# M706K.net
KiCad netlist of a schematic drawn in EAGLE
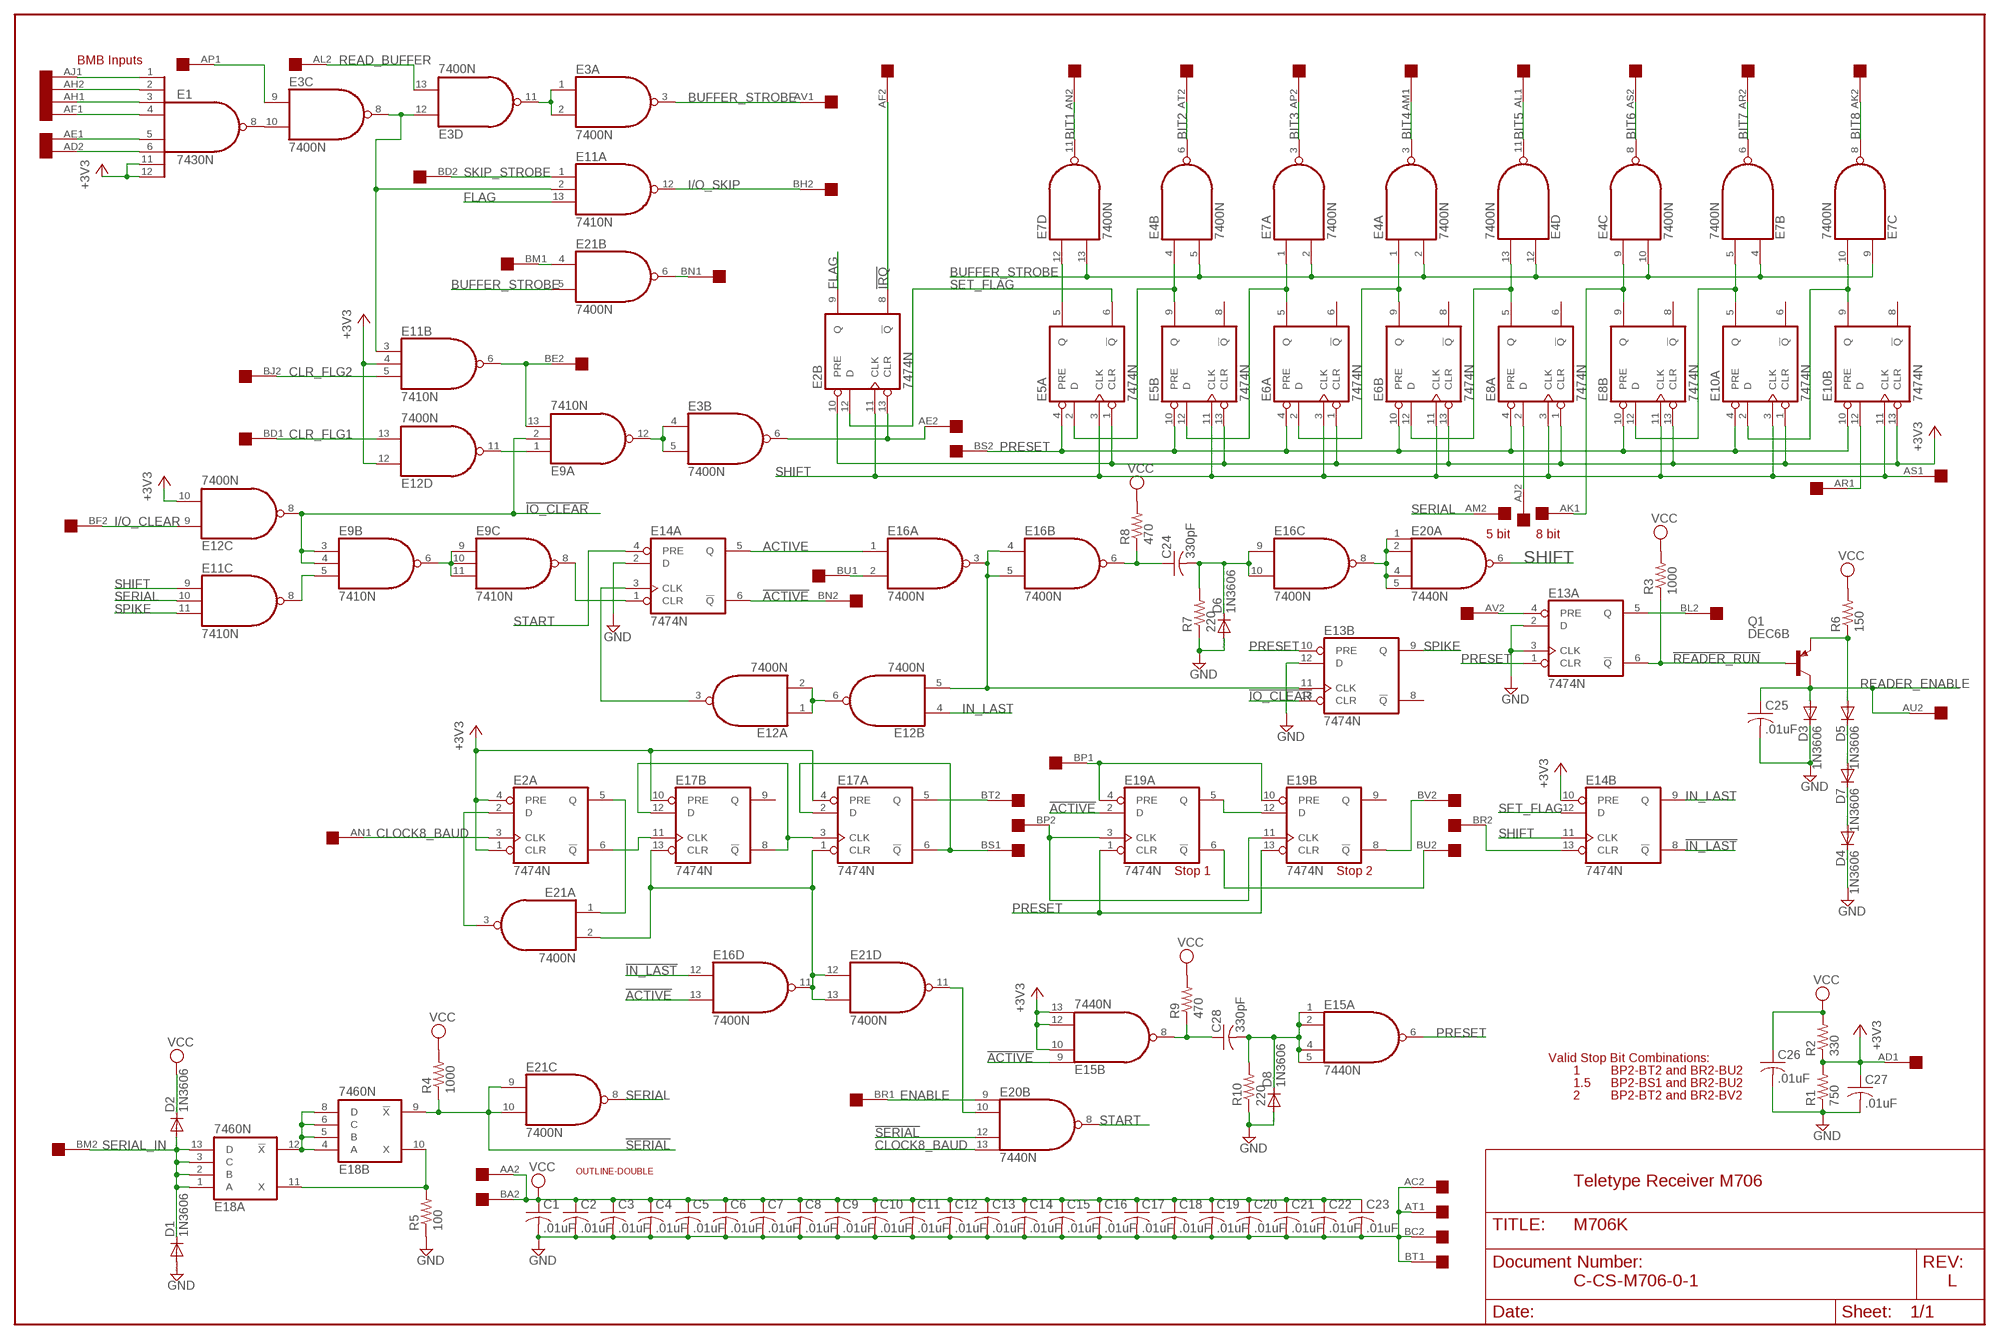
[diagram p0: schematic, sheet 1]

(export (version "E")
  (design (tool "Eeschema 10.0.6"))
  (components
    (comp (ref "C1")
      (value ".01uF")
      (footprint "eagle-import:C050-025X075")
      (libsource (lib "eagle-import") (part "C-US050-025X075"))
    )
    (comp (ref "C2")
      (value ".01uF")
      (footprint "eagle-import:C050-025X075")
      (libsource (lib "eagle-import") (part "C-US050-025X075"))
    )
    (comp (ref "C3")
      (value ".01uF")
      (footprint "eagle-import:C050-025X075")
      (libsource (lib "eagle-import") (part "C-US050-025X075"))
    )
    (comp (ref "C4")
      (value ".01uF")
      (footprint "eagle-import:C050-025X075")
      (libsource (lib "eagle-import") (part "C-US050-025X075"))
    )
    (comp (ref "C5")
      (value ".01uF")
      (footprint "eagle-import:C050-025X075")
      (libsource (lib "eagle-import") (part "C-US050-025X075"))
    )
    (comp (ref "C6")
      (value ".01uF")
      (footprint "eagle-import:C050-025X075")
      (libsource (lib "eagle-import") (part "C-US050-025X075"))
    )
    (comp (ref "C7")
      (value ".01uF")
      (footprint "eagle-import:C050-025X075")
      (libsource (lib "eagle-import") (part "C-US050-025X075"))
    )
    (comp (ref "C8")
      (value ".01uF")
      (footprint "eagle-import:C050-025X075")
      (libsource (lib "eagle-import") (part "C-US050-025X075"))
    )
    (comp (ref "C9")
      (value ".01uF")
      (footprint "eagle-import:C050-025X075")
      (libsource (lib "eagle-import") (part "C-US050-025X075"))
    )
    (comp (ref "C10")
      (value ".01uF")
      (footprint "eagle-import:C050-025X075")
      (libsource (lib "eagle-import") (part "C-US050-025X075"))
    )
    (comp (ref "C11")
      (value ".01uF")
      (footprint "eagle-import:C050-025X075")
      (libsource (lib "eagle-import") (part "C-US050-025X075"))
    )
    (comp (ref "C12")
      (value ".01uF")
      (footprint "eagle-import:C050-025X075")
      (libsource (lib "eagle-import") (part "C-US050-025X075"))
    )
    (comp (ref "C13")
      (value ".01uF")
      (footprint "eagle-import:C050-025X075")
      (libsource (lib "eagle-import") (part "C-US050-025X075"))
    )
    (comp (ref "C14")
      (value ".01uF")
      (footprint "eagle-import:C050-025X075")
      (libsource (lib "eagle-import") (part "C-US050-025X075"))
    )
    (comp (ref "C15")
      (value ".01uF")
      (footprint "eagle-import:C050-025X075")
      (libsource (lib "eagle-import") (part "C-US050-025X075"))
    )
    (comp (ref "C16")
      (value ".01uF")
      (footprint "eagle-import:C050-025X075")
      (libsource (lib "eagle-import") (part "C-US050-025X075"))
    )
    (comp (ref "C17")
      (value ".01uF")
      (footprint "eagle-import:C050-025X075")
      (libsource (lib "eagle-import") (part "C-US050-025X075"))
    )
    (comp (ref "C18")
      (value ".01uF")
      (footprint "eagle-import:C050-025X075")
      (libsource (lib "eagle-import") (part "C-US050-025X075"))
    )
    (comp (ref "C19")
      (value ".01uF")
      (footprint "eagle-import:C050-025X075")
      (libsource (lib "eagle-import") (part "C-US050-025X075"))
    )
    (comp (ref "C20")
      (value ".01uF")
      (footprint "eagle-import:C050-025X075")
      (libsource (lib "eagle-import") (part "C-US050-025X075"))
    )
    (comp (ref "C21")
      (value ".01uF")
      (footprint "eagle-import:C050-025X075")
      (libsource (lib "eagle-import") (part "C-US050-025X075"))
    )
    (comp (ref "C22")
      (value ".01uF")
      (footprint "eagle-import:C050-025X075")
      (libsource (lib "eagle-import") (part "C-US050-025X075"))
    )
    (comp (ref "C23")
      (value ".01uF")
      (footprint "eagle-import:C050-025X075")
      (libsource (lib "eagle-import") (part "C-US050-025X075"))
    )
    (comp (ref "C24")
      (value "330pF")
      (footprint "eagle-import:C050-025X075")
      (libsource (lib "eagle-import") (part "C-US050-025X075"))
    )
    (comp (ref "C25")
      (value ".01uF")
      (footprint "eagle-import:C050-025X075")
      (libsource (lib "eagle-import") (part "C-US050-025X075"))
    )
    (comp (ref "C26")
      (value ".01uF")
      (footprint "eagle-import:C050-025X075")
      (libsource (lib "eagle-import") (part "C-US050-025X075"))
    )
    (comp (ref "C27")
      (value ".01uF")
      (footprint "eagle-import:C050-025X075")
      (libsource (lib "eagle-import") (part "C-US050-025X075"))
    )
    (comp (ref "C28")
      (value "330pF")
      (footprint "eagle-import:C050-025X075")
      (libsource (lib "eagle-import") (part "C-US050-025X075"))
    )
    (comp (ref "D1")
      (value "1N3606")
      (footprint "eagle-import:DO35-10")
      (libsource (lib "eagle-import") (part "1N4148DO35-10"))
    )
    (comp (ref "D2")
      (value "1N3606")
      (footprint "eagle-import:DO35-10")
      (libsource (lib "eagle-import") (part "1N4148DO35-10"))
    )
    (comp (ref "D3")
      (value "1N3606")
      (footprint "eagle-import:DO35-10")
      (libsource (lib "eagle-import") (part "1N4148DO35-10"))
    )
    (comp (ref "D4")
      (value "1N3606")
      (footprint "eagle-import:DO35-10")
      (libsource (lib "eagle-import") (part "1N4148DO35-10"))
    )
    (comp (ref "D5")
      (value "1N3606")
      (footprint "eagle-import:DO35-10")
      (libsource (lib "eagle-import") (part "1N4148DO35-10"))
    )
    (comp (ref "D6")
      (value "1N3606")
      (footprint "eagle-import:DO35-10")
      (libsource (lib "eagle-import") (part "1N4148DO35-10"))
    )
    (comp (ref "D7")
      (value "1N3606")
      (footprint "eagle-import:DO35-10")
      (libsource (lib "eagle-import") (part "1N4148DO35-10"))
    )
    (comp (ref "D8")
      (value "1N3606")
      (footprint "eagle-import:DO35-10")
      (libsource (lib "eagle-import") (part "1N4148DO35-10"))
    )
    (comp (ref "E1")
      (value "7430N")
      (footprint "eagle-import:DIL14")
      (libsource (lib "eagle-import") (part "7430N"))
    )
    (comp (ref "E2")
      (value "7474N")
      (footprint "eagle-import:DIL14")
      (libsource (lib "eagle-import") (part "7474NS"))
    )
    (comp (ref "E3")
      (value "7400N")
      (footprint "eagle-import:DIL14")
      (libsource (lib "eagle-import") (part "7400N"))
    )
    (comp (ref "E4")
      (value "7400N")
      (footprint "eagle-import:DIL14")
      (libsource (lib "eagle-import") (part "7400N"))
    )
    (comp (ref "E5")
      (value "7474N")
      (footprint "eagle-import:DIL14")
      (libsource (lib "eagle-import") (part "7474NS"))
    )
    (comp (ref "E6")
      (value "7474N")
      (footprint "eagle-import:DIL14")
      (libsource (lib "eagle-import") (part "7474NS"))
    )
    (comp (ref "E7")
      (value "7400N")
      (footprint "eagle-import:DIL14")
      (libsource (lib "eagle-import") (part "7400N"))
    )
    (comp (ref "E8")
      (value "7474N")
      (footprint "eagle-import:DIL14")
      (libsource (lib "eagle-import") (part "7474NS"))
    )
    (comp (ref "E9")
      (value "7410N")
      (footprint "eagle-import:DIL14")
      (libsource (lib "eagle-import") (part "7410N"))
    )
    (comp (ref "E10")
      (value "7474N")
      (footprint "eagle-import:DIL14")
      (libsource (lib "eagle-import") (part "7474NS"))
    )
    (comp (ref "E11")
      (value "7410N")
      (footprint "eagle-import:DIL14")
      (libsource (lib "eagle-import") (part "7410N"))
    )
    (comp (ref "E12")
      (value "7400N")
      (footprint "eagle-import:DIL14")
      (libsource (lib "eagle-import") (part "7400N"))
    )
    (comp (ref "E13")
      (value "7474N")
      (footprint "eagle-import:DIL14")
      (libsource (lib "eagle-import") (part "7474NS"))
    )
    (comp (ref "E14")
      (value "7474N")
      (footprint "eagle-import:DIL14")
      (libsource (lib "eagle-import") (part "7474NS"))
    )
    (comp (ref "E15")
      (value "7440N")
      (footprint "eagle-import:DIL14")
      (libsource (lib "eagle-import") (part "7420NS"))
    )
    (comp (ref "E16")
      (value "7400N")
      (footprint "eagle-import:DIL14")
      (libsource (lib "eagle-import") (part "7400N"))
    )
    (comp (ref "E17")
      (value "7474N")
      (footprint "eagle-import:DIL14")
      (libsource (lib "eagle-import") (part "7474NS"))
    )
    (comp (ref "E18")
      (value "7460N")
      (footprint "eagle-import:DIL14")
      (libsource (lib "eagle-import") (part "7460N"))
    )
    (comp (ref "E19")
      (value "7474N")
      (footprint "eagle-import:DIL14")
      (libsource (lib "eagle-import") (part "7474NS"))
    )
    (comp (ref "E20")
      (value "7440N")
      (footprint "eagle-import:DIL14")
      (libsource (lib "eagle-import") (part "7420NS"))
    )
    (comp (ref "E21")
      (value "7400N")
      (footprint "eagle-import:DIL14")
      (libsource (lib "eagle-import") (part "7400N"))
    )
    (comp (ref "Q1")
      (value "DEC6B")
      (footprint "eagle-import:TO39")
      (libsource (lib "eagle-import") (part "2N2904"))
    )
    (comp (ref "R1")
      (value "750")
      (footprint "eagle-import:0207_10")
      (libsource (lib "eagle-import") (part "R-US_0207/10"))
    )
    (comp (ref "R2")
      (value "330")
      (footprint "eagle-import:0207_10")
      (libsource (lib "eagle-import") (part "R-US_0207/10"))
    )
    (comp (ref "R3")
      (value "1000")
      (footprint "eagle-import:0207_10")
      (libsource (lib "eagle-import") (part "R-US_0207/10"))
    )
    (comp (ref "R4")
      (value "1000")
      (footprint "eagle-import:0207_10")
      (libsource (lib "eagle-import") (part "R-US_0207/10"))
    )
    (comp (ref "R5")
      (value "100")
      (footprint "eagle-import:0207_10")
      (libsource (lib "eagle-import") (part "R-US_0207/10"))
    )
    (comp (ref "R6")
      (value "150")
      (footprint "eagle-import:0207_10")
      (libsource (lib "eagle-import") (part "R-US_0207/10"))
    )
    (comp (ref "R7")
      (value "220")
      (footprint "eagle-import:0207_10")
      (libsource (lib "eagle-import") (part "R-US_0207/10"))
    )
    (comp (ref "R8")
      (value "470")
      (footprint "eagle-import:0207_10")
      (libsource (lib "eagle-import") (part "R-US_0207/10"))
    )
    (comp (ref "R9")
      (value "470")
      (footprint "eagle-import:0207_10")
      (libsource (lib "eagle-import") (part "R-US_0207/10"))
    )
    (comp (ref "R10")
      (value "220")
      (footprint "eagle-import:0207_10")
      (libsource (lib "eagle-import") (part "R-US_0207/10"))
    )
    (comp (ref "U$1")
      (value "OUTLINE-DOUBLE")
      (footprint "eagle-import:DOUBLE")
      (libsource (lib "eagle-import") (part "OUTLINE-DOUBLE"))
    )
    (comp (ref "U$2")
      (value "DOUBLE")
      (footprint "eagle-import:EDGE-CON4")
      (libsource (lib "eagle-import") (part "DOUBLE"))
    )
  )
  (nets
    (net (code "1") (name "+3V3") (class "Default")
      (node (ref "C27") (pin "1") (pinfunction "1_1") (pintype "passive"))
      (node (ref "E1") (pin "11") (pinfunction "I6_11") (pintype "input"))
      (node (ref "E1") (pin "12") (pinfunction "I7_12") (pintype "input"))
      (node (ref "E10") (pin "1") (pinfunction "CLR_1") (pintype "input"))
      (node (ref "E10") (pin "13") (pinfunction "CLR_13") (pintype "input"))
      (node (ref "E11") (pin "4") (pinfunction "I1_4") (pintype "input"))
      (node (ref "E12") (pin "10") (pinfunction "I1_10") (pintype "input"))
      (node (ref "E12") (pin "12") (pinfunction "I0_12") (pintype "input"))
      (node (ref "E14") (pin "10") (pinfunction "PRE_10") (pintype "input"))
      (node (ref "E15") (pin "10") (pinfunction "I1_10") (pintype "input"))
      (node (ref "E15") (pin "12") (pinfunction "I2_12") (pintype "input"))
      (node (ref "E15") (pin "13") (pinfunction "I3_13") (pintype "input"))
      (node (ref "E17") (pin "10") (pinfunction "PRE_10") (pintype "input"))
      (node (ref "E17") (pin "4") (pinfunction "PRE_4") (pintype "input"))
      (node (ref "E2") (pin "1") (pinfunction "CLR_1") (pintype "input"))
      (node (ref "E2") (pin "10") (pinfunction "PRE_10") (pintype "input"))
      (node (ref "E2") (pin "4") (pinfunction "PRE_4") (pintype "input"))
      (node (ref "E5") (pin "1") (pinfunction "CLR_1") (pintype "input"))
      (node (ref "E5") (pin "13") (pinfunction "CLR_13") (pintype "input"))
      (node (ref "E6") (pin "1") (pinfunction "CLR_1") (pintype "input"))
      (node (ref "E6") (pin "13") (pinfunction "CLR_13") (pintype "input"))
      (node (ref "E8") (pin "1") (pinfunction "CLR_1") (pintype "input"))
      (node (ref "E8") (pin "13") (pinfunction "CLR_13") (pintype "input"))
      (node (ref "R1") (pin "2") (pinfunction "2_2") (pintype "passive"))
      (node (ref "R2") (pin "1") (pinfunction "1_1") (pintype "passive"))
      (node (ref "U$2") (pin "AD1") (pinfunction "1_AD1") (pintype "bidirectional"))
    )
    (net (code "2") (name "/ACTIVE") (class "Default")
      (node (ref "E14") (pin "5") (pinfunction "Q_5") (pintype "output"))
      (node (ref "E16") (pin "1") (pinfunction "I0_1") (pintype "input"))
    )
    (net (code "3") (name "/BIT1") (class "Default")
      (node (ref "E7") (pin "11") (pinfunction "O_11") (pintype "output"))
      (node (ref "U$2") (pin "AN2") (pinfunction "1_AN2") (pintype "bidirectional"))
    )
    (net (code "4") (name "/BIT2") (class "Default")
      (node (ref "E4") (pin "6") (pinfunction "O_6") (pintype "output"))
      (node (ref "U$2") (pin "AT2") (pinfunction "1_AT2") (pintype "bidirectional"))
    )
    (net (code "5") (name "/BIT3") (class "Default")
      (node (ref "E7") (pin "3") (pinfunction "O_3") (pintype "output"))
      (node (ref "U$2") (pin "AP2") (pinfunction "1_AP2") (pintype "bidirectional"))
    )
    (net (code "6") (name "/BIT4") (class "Default")
      (node (ref "E4") (pin "3") (pinfunction "O_3") (pintype "output"))
      (node (ref "U$2") (pin "AM1") (pinfunction "1_AM1") (pintype "bidirectional"))
    )
    (net (code "7") (name "/BIT5") (class "Default")
      (node (ref "E4") (pin "11") (pinfunction "O_11") (pintype "output"))
      (node (ref "U$2") (pin "AL1") (pinfunction "1_AL1") (pintype "bidirectional"))
    )
    (net (code "8") (name "/BIT6") (class "Default")
      (node (ref "E4") (pin "8") (pinfunction "O_8") (pintype "output"))
      (node (ref "U$2") (pin "AS2") (pinfunction "1_AS2") (pintype "bidirectional"))
    )
    (net (code "9") (name "/BIT7") (class "Default")
      (node (ref "E7") (pin "6") (pinfunction "O_6") (pintype "output"))
      (node (ref "U$2") (pin "AR2") (pinfunction "1_AR2") (pintype "bidirectional"))
    )
    (net (code "10") (name "/BIT8") (class "Default")
      (node (ref "E7") (pin "8") (pinfunction "O_8") (pintype "output"))
      (node (ref "U$2") (pin "AK2") (pinfunction "1_AK2") (pintype "bidirectional"))
    )
    (net (code "11") (name "/BUFFER_STROBE") (class "Default")
      (node (ref "E21") (pin "5") (pinfunction "I1_5") (pintype "input"))
      (node (ref "E3") (pin "3") (pinfunction "O_3") (pintype "output"))
      (node (ref "E4") (pin "10") (pinfunction "I1_10") (pintype "input"))
      (node (ref "E4") (pin "12") (pinfunction "I0_12") (pintype "input"))
      (node (ref "E4") (pin "2") (pinfunction "I1_2") (pintype "input"))
      (node (ref "E4") (pin "5") (pinfunction "I1_5") (pintype "input"))
      (node (ref "E7") (pin "13") (pinfunction "I1_13") (pintype "input"))
      (node (ref "E7") (pin "2") (pinfunction "I1_2") (pintype "input"))
      (node (ref "E7") (pin "4") (pinfunction "I0_4") (pintype "input"))
      (node (ref "E7") (pin "9") (pinfunction "I0_9") (pintype "input"))
      (node (ref "U$2") (pin "AV1") (pinfunction "1_AV1") (pintype "bidirectional"))
    )
    (net (code "12") (name "/CLOCK8_BAUD") (class "Default")
      (node (ref "E2") (pin "3") (pinfunction "CLK_3") (pintype "input"))
      (node (ref "E20") (pin "13") (pinfunction "I3_13") (pintype "input"))
      (node (ref "U$2") (pin "AN1") (pinfunction "1_AN1") (pintype "bidirectional"))
    )
    (net (code "13") (name "/CLR_FLG1") (class "Default")
      (node (ref "E12") (pin "13") (pinfunction "I1_13") (pintype "input"))
      (node (ref "U$2") (pin "BD1") (pinfunction "1_BD1") (pintype "bidirectional"))
    )
    (net (code "14") (name "/CLR_FLG2") (class "Default")
      (node (ref "E11") (pin "5") (pinfunction "I2_5") (pintype "input"))
      (node (ref "U$2") (pin "BJ2") (pinfunction "1_BJ2") (pintype "bidirectional"))
    )
    (net (code "15") (name "/ENABLE") (class "Default")
      (node (ref "E20") (pin "9") (pinfunction "I0_9") (pintype "input"))
      (node (ref "U$2") (pin "BR1") (pinfunction "1_BR1") (pintype "bidirectional"))
    )
    (net (code "16") (name "/FLAG") (class "Default")
      (node (ref "E11") (pin "13") (pinfunction "I2_13") (pintype "input"))
      (node (ref "E2") (pin "9") (pinfunction "Q_9") (pintype "output"))
    )
    (net (code "17") (name "/IN_LAST") (class "Default")
      (node (ref "E12") (pin "4") (pinfunction "I0_4") (pintype "input"))
      (node (ref "E14") (pin "9") (pinfunction "Q_9") (pintype "output"))
    )
    (net (code "18") (name "/I{slash}O_CLEAR") (class "Default")
      (node (ref "E12") (pin "9") (pinfunction "I0_9") (pintype "input"))
      (node (ref "U$2") (pin "BF2") (pinfunction "1_BF2") (pintype "bidirectional"))
    )
    (net (code "19") (name "/I{slash}O_SKIP") (class "Default")
      (node (ref "E11") (pin "12") (pinfunction "O_12") (pintype "output"))
      (node (ref "U$2") (pin "BH2") (pinfunction "1_BH2") (pintype "bidirectional"))
    )
    (net (code "20") (name "/PRESET") (class "Default")
      (node (ref "E10") (pin "10") (pinfunction "PRE_10") (pintype "input"))
      (node (ref "E10") (pin "4") (pinfunction "PRE_4") (pintype "input"))
      (node (ref "E13") (pin "1") (pinfunction "CLR_1") (pintype "input"))
      (node (ref "E13") (pin "10") (pinfunction "PRE_10") (pintype "input"))
      (node (ref "E15") (pin "6") (pinfunction "O_6") (pintype "output"))
      (node (ref "E19") (pin "1") (pinfunction "CLR_1") (pintype "input"))
      (node (ref "E19") (pin "13") (pinfunction "CLR_13") (pintype "input"))
      (node (ref "E5") (pin "10") (pinfunction "PRE_10") (pintype "input"))
      (node (ref "E5") (pin "4") (pinfunction "PRE_4") (pintype "input"))
      (node (ref "E6") (pin "10") (pinfunction "PRE_10") (pintype "input"))
      (node (ref "E6") (pin "4") (pinfunction "PRE_4") (pintype "input"))
      (node (ref "E8") (pin "10") (pinfunction "PRE_10") (pintype "input"))
      (node (ref "E8") (pin "4") (pinfunction "PRE_4") (pintype "input"))
      (node (ref "U$2") (pin "BS2") (pinfunction "1_BS2") (pintype "bidirectional"))
    )
    (net (code "21") (name "/READER_ENABLE") (class "Default")
      (node (ref "C25") (pin "1") (pinfunction "1_1") (pintype "passive"))
      (node (ref "D3") (pin "A") (pinfunction "A_A") (pintype "passive"))
      (node (ref "Q1") (pin "3") (pinfunction "C_3") (pintype "passive"))
      (node (ref "U$2") (pin "AU2") (pinfunction "1_AU2") (pintype "bidirectional"))
    )
    (net (code "22") (name "/READ_BUFFER") (class "Default")
      (node (ref "E3") (pin "13") (pinfunction "I1_13") (pintype "input"))
      (node (ref "U$2") (pin "AL2") (pinfunction "1_AL2") (pintype "bidirectional"))
    )
    (net (code "23") (name "/SERIAL") (class "Default")
      (node (ref "E11") (pin "10") (pinfunction "I1_10") (pintype "input"))
      (node (ref "E21") (pin "8") (pinfunction "O_8") (pintype "output"))
      (node (ref "U$2") (pin "AM2") (pinfunction "1_AM2") (pintype "bidirectional"))
    )
    (net (code "24") (name "/SERIAL_IN") (class "Default")
      (node (ref "D1") (pin "C") (pinfunction "C_C") (pintype "passive"))
      (node (ref "D2") (pin "A") (pinfunction "A_A") (pintype "passive"))
      (node (ref "E18") (pin "1") (pinfunction "A_1") (pintype "input"))
      (node (ref "E18") (pin "13") (pinfunction "D_13") (pintype "input"))
      (node (ref "E18") (pin "2") (pinfunction "B_2") (pintype "input"))
      (node (ref "E18") (pin "3") (pinfunction "C_3") (pintype "input"))
      (node (ref "U$2") (pin "BM2") (pinfunction "1_BM2") (pintype "bidirectional"))
    )
    (net (code "25") (name "/SET_FLAG") (class "Default")
      (node (ref "E14") (pin "12") (pinfunction "D_12") (pintype "input"))
      (node (ref "E2") (pin "12") (pinfunction "D_12") (pintype "input"))
      (node (ref "E5") (pin "6") (pinfunction "~{Q}_6") (pintype "output"))
    )
    (net (code "26") (name "/SHIFT") (class "Default")
      (node (ref "E10") (pin "11") (pinfunction "CLK_11") (pintype "input"))
      (node (ref "E10") (pin "3") (pinfunction "CLK_3") (pintype "input"))
      (node (ref "E11") (pin "9") (pinfunction "I0_9") (pintype "input"))
      (node (ref "E14") (pin "11") (pinfunction "CLK_11") (pintype "input"))
      (node (ref "E2") (pin "11") (pinfunction "CLK_11") (pintype "input"))
      (node (ref "E20") (pin "6") (pinfunction "O_6") (pintype "output"))
      (node (ref "E5") (pin "11") (pinfunction "CLK_11") (pintype "input"))
      (node (ref "E5") (pin "3") (pinfunction "CLK_3") (pintype "input"))
      (node (ref "E6") (pin "11") (pinfunction "CLK_11") (pintype "input"))
      (node (ref "E6") (pin "3") (pinfunction "CLK_3") (pintype "input"))
      (node (ref "E8") (pin "11") (pinfunction "CLK_11") (pintype "input"))
      (node (ref "E8") (pin "3") (pinfunction "CLK_3") (pintype "input"))
      (node (ref "U$2") (pin "AS1") (pinfunction "1_AS1") (pintype "bidirectional"))
    )
    (net (code "27") (name "/SKIP_STROBE") (class "Default")
      (node (ref "E11") (pin "1") (pinfunction "I0_1") (pintype "input"))
      (node (ref "U$2") (pin "BD2") (pinfunction "1_BD2") (pintype "bidirectional"))
    )
    (net (code "28") (name "/SPIKE") (class "Default")
      (node (ref "E11") (pin "11") (pinfunction "I2_11") (pintype "input"))
      (node (ref "E13") (pin "9") (pinfunction "Q_9") (pintype "output"))
    )
    (net (code "29") (name "/START") (class "Default")
      (node (ref "E14") (pin "4") (pinfunction "PRE_4") (pintype "input"))
      (node (ref "E20") (pin "8") (pinfunction "O_8") (pintype "output"))
    )
    (net (code "30") (name "/~{ACTIVE}") (class "Default")
      (node (ref "E14") (pin "6") (pinfunction "~{Q}_6") (pintype "output"))
      (node (ref "E15") (pin "9") (pinfunction "I0_9") (pintype "input"))
      (node (ref "E16") (pin "13") (pinfunction "I1_13") (pintype "input"))
      (node (ref "E19") (pin "2") (pinfunction "D_2") (pintype "input"))
      (node (ref "U$2") (pin "BN2") (pinfunction "1_BN2") (pintype "bidirectional"))
    )
    (net (code "31") (name "/~{IN_LAST}") (class "Default")
      (node (ref "E14") (pin "8") (pinfunction "~{Q}_8") (pintype "output"))
      (node (ref "E16") (pin "12") (pinfunction "I0_12") (pintype "input"))
    )
    (net (code "32") (name "/~{IO_CLEAR}") (class "Default")
      (node (ref "E12") (pin "8") (pinfunction "O_8") (pintype "output"))
      (node (ref "E13") (pin "13") (pinfunction "CLR_13") (pintype "input"))
      (node (ref "E9") (pin "2") (pinfunction "I1_2") (pintype "input"))
      (node (ref "E9") (pin "3") (pinfunction "I0_3") (pintype "input"))
      (node (ref "E9") (pin "4") (pinfunction "I1_4") (pintype "input"))
    )
    (net (code "33") (name "/~{IRQ}") (class "Default")
      (node (ref "E2") (pin "8") (pinfunction "~{Q}_8") (pintype "output"))
      (node (ref "U$2") (pin "AF2") (pinfunction "1_AF2") (pintype "bidirectional"))
    )
    (net (code "34") (name "/~{READER_RUN}") (class "Default")
      (node (ref "E13") (pin "6") (pinfunction "~{Q}_6") (pintype "output"))
      (node (ref "Q1") (pin "2") (pinfunction "B_2") (pintype "passive"))
      (node (ref "R3") (pin "1") (pinfunction "1_1") (pintype "passive"))
    )
    (net (code "35") (name "/~{SERIAL}") (class "Default")
      (node (ref "E18") (pin "9") (pinfunction "~{X}_9") (pintype "output"))
      (node (ref "E20") (pin "12") (pinfunction "I2_12") (pintype "input"))
      (node (ref "E21") (pin "10") (pinfunction "I1_10") (pintype "input"))
      (node (ref "E21") (pin "9") (pinfunction "I0_9") (pintype "input"))
      (node (ref "R4") (pin "1") (pinfunction "1_1") (pintype "passive"))
    )
    (net (code "36") (name "GND") (class "Default")
      (node (ref "C1") (pin "2") (pinfunction "2_2") (pintype "passive"))
      (node (ref "C10") (pin "2") (pinfunction "2_2") (pintype "passive"))
      (node (ref "C11") (pin "2") (pinfunction "2_2") (pintype "passive"))
      (node (ref "C12") (pin "2") (pinfunction "2_2") (pintype "passive"))
      (node (ref "C13") (pin "2") (pinfunction "2_2") (pintype "passive"))
      (node (ref "C14") (pin "2") (pinfunction "2_2") (pintype "passive"))
      (node (ref "C15") (pin "2") (pinfunction "2_2") (pintype "passive"))
      (node (ref "C16") (pin "2") (pinfunction "2_2") (pintype "passive"))
      (node (ref "C17") (pin "2") (pinfunction "2_2") (pintype "passive"))
      (node (ref "C18") (pin "2") (pinfunction "2_2") (pintype "passive"))
      (node (ref "C19") (pin "2") (pinfunction "2_2") (pintype "passive"))
      (node (ref "C2") (pin "2") (pinfunction "2_2") (pintype "passive"))
      (node (ref "C20") (pin "2") (pinfunction "2_2") (pintype "passive"))
      (node (ref "C21") (pin "2") (pinfunction "2_2") (pintype "passive"))
      (node (ref "C22") (pin "2") (pinfunction "2_2") (pintype "passive"))
      (node (ref "C23") (pin "2") (pinfunction "2_2") (pintype "passive"))
      (node (ref "C25") (pin "2") (pinfunction "2_2") (pintype "passive"))
      (node (ref "C26") (pin "2") (pinfunction "2_2") (pintype "passive"))
      (node (ref "C27") (pin "2") (pinfunction "2_2") (pintype "passive"))
      (node (ref "C3") (pin "2") (pinfunction "2_2") (pintype "passive"))
      (node (ref "C4") (pin "2") (pinfunction "2_2") (pintype "passive"))
      (node (ref "C5") (pin "2") (pinfunction "2_2") (pintype "passive"))
      (node (ref "C6") (pin "2") (pinfunction "2_2") (pintype "passive"))
      (node (ref "C7") (pin "2") (pinfunction "2_2") (pintype "passive"))
      (node (ref "C8") (pin "2") (pinfunction "2_2") (pintype "passive"))
      (node (ref "C9") (pin "2") (pinfunction "2_2") (pintype "passive"))
      (node (ref "D1") (pin "A") (pinfunction "A_A") (pintype "passive"))
      (node (ref "D3") (pin "C") (pinfunction "C_C") (pintype "passive"))
      (node (ref "D4") (pin "C") (pinfunction "C_C") (pintype "passive"))
      (node (ref "D6") (pin "A") (pinfunction "A_A") (pintype "passive"))
      (node (ref "D8") (pin "A") (pinfunction "A_A") (pintype "passive"))
      (node (ref "E13") (pin "12") (pinfunction "D_12") (pintype "input"))
      (node (ref "E13") (pin "2") (pinfunction "D_2") (pintype "input"))
      (node (ref "E13") (pin "3") (pinfunction "CLK_3") (pintype "input"))
      (node (ref "E14") (pin "2") (pinfunction "D_2") (pintype "input"))
      (node (ref "R1") (pin "1") (pinfunction "1_1") (pintype "passive"))
      (node (ref "R10") (pin "1") (pinfunction "1_1") (pintype "passive"))
      (node (ref "R5") (pin "1") (pinfunction "1_1") (pintype "passive"))
      (node (ref "R7") (pin "1") (pinfunction "1_1") (pintype "passive"))
      (node (ref "U$2") (pin "AC2") (pinfunction "1_AC2") (pintype "bidirectional"))
      (node (ref "U$2") (pin "AT1") (pinfunction "1_AT1") (pintype "bidirectional"))
      (node (ref "U$2") (pin "BC2") (pinfunction "1_BC2") (pintype "bidirectional"))
      (node (ref "U$2") (pin "BT1") (pinfunction "1_BT1") (pintype "bidirectional"))
    )
    (net (code "37") (name "Net-(D4-PadA)") (class "Default")
      (node (ref "D4") (pin "A") (pinfunction "A_A") (pintype "passive"))
      (node (ref "D7") (pin "C") (pinfunction "C_C") (pintype "passive"))
    )
    (net (code "38") (name "Net-(D5-PadC)") (class "Default")
      (node (ref "D5") (pin "C") (pinfunction "C_C") (pintype "passive"))
      (node (ref "D7") (pin "A") (pinfunction "A_A") (pintype "passive"))
    )
    (net (code "39") (name "Net-(E1A-I0)") (class "Default")
      (node (ref "E1") (pin "1") (pinfunction "I0_1") (pintype "input"))
      (node (ref "U$2") (pin "AJ1") (pinfunction "1_AJ1") (pintype "bidirectional"))
    )
    (net (code "40") (name "Net-(E1A-I1)") (class "Default")
      (node (ref "E1") (pin "2") (pinfunction "I1_2") (pintype "input"))
      (node (ref "U$2") (pin "AH2") (pinfunction "1_AH2") (pintype "bidirectional"))
    )
    (net (code "41") (name "Net-(E1A-I2)") (class "Default")
      (node (ref "E1") (pin "3") (pinfunction "I2_3") (pintype "input"))
      (node (ref "U$2") (pin "AH1") (pinfunction "1_AH1") (pintype "bidirectional"))
    )
    (net (code "42") (name "Net-(E1A-I3)") (class "Default")
      (node (ref "E1") (pin "4") (pinfunction "I3_4") (pintype "input"))
      (node (ref "U$2") (pin "AF1") (pinfunction "1_AF1") (pintype "bidirectional"))
    )
    (net (code "43") (name "Net-(E1A-I4)") (class "Default")
      (node (ref "E1") (pin "5") (pinfunction "I4_5") (pintype "input"))
      (node (ref "U$2") (pin "AE1") (pinfunction "1_AE1") (pintype "bidirectional"))
    )
    (net (code "44") (name "Net-(E1A-I5)") (class "Default")
      (node (ref "E1") (pin "6") (pinfunction "I5_6") (pintype "input"))
      (node (ref "U$2") (pin "AD2") (pinfunction "1_AD2") (pintype "bidirectional"))
    )
    (net (code "45") (name "Net-(E1A-O)") (class "Default")
      (node (ref "E1") (pin "8") (pinfunction "O_8") (pintype "output"))
      (node (ref "E3") (pin "10") (pinfunction "I1_10") (pintype "input"))
    )
    (net (code "46") (name "Net-(E2B-CLR)") (class "Default")
      (node (ref "E2") (pin "13") (pinfunction "CLR_13") (pintype "input"))
      (node (ref "E3") (pin "6") (pinfunction "O_6") (pintype "output"))
      (node (ref "U$2") (pin "AE2") (pinfunction "1_AE2") (pintype "bidirectional"))
    )
    (net (code "47") (name "Net-(E3A-I0)") (class "Default")
      (node (ref "E3") (pin "1") (pinfunction "I0_1") (pintype "input"))
      (node (ref "E3") (pin "11") (pinfunction "O_11") (pintype "output"))
      (node (ref "E3") (pin "2") (pinfunction "I1_2") (pintype "input"))
    )
    (net (code "48") (name "Net-(E3B-I0)") (class "Default")
      (node (ref "E3") (pin "4") (pinfunction "I0_4") (pintype "input"))
      (node (ref "E3") (pin "5") (pinfunction "I1_5") (pintype "input"))
      (node (ref "E9") (pin "12") (pinfunction "O_12") (pintype "output"))
    )
    (net (code "49") (name "Net-(E3C-I0)") (class "Default")
      (node (ref "E3") (pin "9") (pinfunction "I0_9") (pintype "input"))
      (node (ref "U$2") (pin "AP1") (pinfunction "1_AP1") (pintype "bidirectional"))
    )
    (net (code "50") (name "Net-(E4A-I0)") (class "Default")
      (node (ref "E4") (pin "1") (pinfunction "I0_1") (pintype "input"))
      (node (ref "E6") (pin "2") (pinfunction "D_2") (pintype "input"))
      (node (ref "E6") (pin "9") (pinfunction "Q_9") (pintype "output"))
    )
    (net (code "51") (name "Net-(E4B-I0)") (class "Default")
      (node (ref "E4") (pin "4") (pinfunction "I0_4") (pintype "input"))
      (node (ref "E5") (pin "2") (pinfunction "D_2") (pintype "input"))
      (node (ref "E5") (pin "9") (pinfunction "Q_9") (pintype "output"))
    )
    (net (code "52") (name "Net-(E4C-I0)") (class "Default")
      (node (ref "E4") (pin "9") (pinfunction "I0_9") (pintype "input"))
      (node (ref "E8") (pin "9") (pinfunction "Q_9") (pintype "output"))
      (node (ref "U$2") (pin "AK1") (pinfunction "1_AK1") (pintype "bidirectional"))
    )
    (net (code "53") (name "Net-(E4D-I1)") (class "Default")
      (node (ref "E4") (pin "13") (pinfunction "I1_13") (pintype "input"))
      (node (ref "E6") (pin "12") (pinfunction "D_12") (pintype "input"))
      (node (ref "E8") (pin "5") (pinfunction "Q_5") (pintype "output"))
    )
    (net (code "54") (name "Net-(E5A-Q)") (class "Default")
      (node (ref "E5") (pin "5") (pinfunction "Q_5") (pintype "output"))
      (node (ref "E7") (pin "12") (pinfunction "I0_12") (pintype "input"))
    )
    (net (code "55") (name "Net-(E5B-D)") (class "Default")
      (node (ref "E5") (pin "12") (pinfunction "D_12") (pintype "input"))
      (node (ref "E6") (pin "5") (pinfunction "Q_5") (pintype "output"))
      (node (ref "E7") (pin "1") (pinfunction "I0_1") (pintype "input"))
    )
    (net (code "56") (name "Net-(E8A-D)") (class "Default")
      (node (ref "E8") (pin "2") (pinfunction "D_2") (pintype "input"))
      (node (ref "U$2") (pin "AJ2") (pinfunction "1_AJ2") (pintype "bidirectional"))
    )
    (net (code "57") (name "Net-(E9B-O)") (class "Default")
      (node (ref "E9") (pin "10") (pinfunction "I1_10") (pintype "input"))
      (node (ref "E9") (pin "11") (pinfunction "I2_11") (pintype "input"))
      (node (ref "E9") (pin "6") (pinfunction "O_6") (pintype "output"))
      (node (ref "E9") (pin "9") (pinfunction "I0_9") (pintype "input"))
    )
    (net (code "58") (name "Net-(E10A-D)") (class "Default")
      (node (ref "E10") (pin "2") (pinfunction "D_2") (pintype "input"))
      (node (ref "E10") (pin "9") (pinfunction "Q_9") (pintype "output"))
      (node (ref "E7") (pin "10") (pinfunction "I1_10") (pintype "input"))
    )
    (net (code "59") (name "Net-(E10A-Q)") (class "Default")
      (node (ref "E10") (pin "5") (pinfunction "Q_5") (pintype "output"))
      (node (ref "E7") (pin "5") (pinfunction "I1_5") (pintype "input"))
      (node (ref "E8") (pin "12") (pinfunction "D_12") (pintype "input"))
    )
    (net (code "60") (name "Net-(E10B-D)") (class "Default")
      (node (ref "E10") (pin "12") (pinfunction "D_12") (pintype "input"))
      (node (ref "U$2") (pin "AR1") (pinfunction "1_AR1") (pintype "bidirectional"))
    )
    (net (code "61") (name "Net-(E11A-I1)") (class "Default")
      (node (ref "E11") (pin "2") (pinfunction "I1_2") (pintype "input"))
      (node (ref "E11") (pin "3") (pinfunction "I0_3") (pintype "input"))
      (node (ref "E3") (pin "12") (pinfunction "I0_12") (pintype "input"))
      (node (ref "E3") (pin "8") (pinfunction "O_8") (pintype "output"))
    )
    (net (code "62") (name "Net-(E11B-O)") (class "Default")
      (node (ref "E11") (pin "6") (pinfunction "O_6") (pintype "output"))
      (node (ref "E9") (pin "13") (pinfunction "I2_13") (pintype "input"))
      (node (ref "U$2") (pin "BE2") (pinfunction "1_BE2") (pintype "bidirectional"))
    )
    (net (code "63") (name "Net-(E11C-O)") (class "Default")
      (node (ref "E11") (pin "8") (pinfunction "O_8") (pintype "output"))
      (node (ref "E9") (pin "5") (pinfunction "I2_5") (pintype "input"))
    )
    (net (code "64") (name "Net-(E12A-I0)") (class "Default")
      (node (ref "E12") (pin "1") (pinfunction "I0_1") (pintype "input"))
      (node (ref "E12") (pin "2") (pinfunction "I1_2") (pintype "input"))
      (node (ref "E12") (pin "6") (pinfunction "O_6") (pintype "output"))
    )
    (net (code "65") (name "Net-(E12A-O)") (class "Default")
      (node (ref "E12") (pin "3") (pinfunction "O_3") (pintype "output"))
      (node (ref "E14") (pin "3") (pinfunction "CLK_3") (pintype "input"))
    )
    (net (code "66") (name "Net-(E12B-I1)") (class "Default")
      (node (ref "E12") (pin "5") (pinfunction "I1_5") (pintype "input"))
      (node (ref "E13") (pin "11") (pinfunction "CLK_11") (pintype "input"))
      (node (ref "E16") (pin "3") (pinfunction "O_3") (pintype "output"))
      (node (ref "E16") (pin "4") (pinfunction "I0_4") (pintype "input"))
      (node (ref "E16") (pin "5") (pinfunction "I1_5") (pintype "input"))
    )
    (net (code "67") (name "Net-(E12D-O)") (class "Default")
      (node (ref "E12") (pin "11") (pinfunction "O_11") (pintype "output"))
      (node (ref "E9") (pin "1") (pinfunction "I0_1") (pintype "input"))
    )
    (net (code "68") (name "Net-(E13A-PRE)") (class "Default")
      (node (ref "E13") (pin "4") (pinfunction "PRE_4") (pintype "input"))
      (node (ref "U$2") (pin "AV2") (pinfunction "1_AV2") (pintype "bidirectional"))
    )
    (net (code "69") (name "Net-(E13A-Q)") (class "Default")
      (node (ref "E13") (pin "5") (pinfunction "Q_5") (pintype "output"))
      (node (ref "U$2") (pin "BL2") (pinfunction "1_BL2") (pintype "bidirectional"))
    )
    (net (code "70") (name "Net-(E14A-CLR)") (class "Default")
      (node (ref "E14") (pin "1") (pinfunction "CLR_1") (pintype "input"))
      (node (ref "E9") (pin "8") (pinfunction "O_8") (pintype "output"))
    )
    (net (code "71") (name "Net-(E14B-CLR)") (class "Default")
      (node (ref "E14") (pin "13") (pinfunction "CLR_13") (pintype "input"))
      (node (ref "U$2") (pin "BR2") (pinfunction "1_BR2") (pintype "bidirectional"))
    )
    (net (code "72") (name "Net-(E15A-I0)") (class "Default")
      (node (ref "C28") (pin "2") (pinfunction "2_2") (pintype "passive"))
      (node (ref "D8") (pin "C") (pinfunction "C_C") (pintype "passive"))
      (node (ref "E15") (pin "1") (pinfunction "I0_1") (pintype "input"))
      (node (ref "E15") (pin "2") (pinfunction "I1_2") (pintype "input"))
      (node (ref "E15") (pin "4") (pinfunction "I2_4") (pintype "input"))
      (node (ref "E15") (pin "5") (pinfunction "I3_5") (pintype "input"))
      (node (ref "R10") (pin "2") (pinfunction "2_2") (pintype "passive"))
    )
    (net (code "73") (name "Net-(E15B-O)") (class "Default")
      (node (ref "C28") (pin "1") (pinfunction "1_1") (pintype "passive"))
      (node (ref "E15") (pin "8") (pinfunction "O_8") (pintype "output"))
      (node (ref "R9") (pin "1") (pinfunction "1_1") (pintype "passive"))
    )
    (net (code "74") (name "Net-(E16A-I1)") (class "Default")
      (node (ref "E16") (pin "2") (pinfunction "I1_2") (pintype "input"))
      (node (ref "U$2") (pin "BU1") (pinfunction "1_BU1") (pintype "bidirectional"))
    )
    (net (code "75") (name "Net-(E16B-O)") (class "Default")
      (node (ref "C24") (pin "1") (pinfunction "1_1") (pintype "passive"))
      (node (ref "E16") (pin "6") (pinfunction "O_6") (pintype "output"))
      (node (ref "R8") (pin "1") (pinfunction "1_1") (pintype "passive"))
    )
    (net (code "76") (name "Net-(E16C-I0)") (class "Default")
      (node (ref "C24") (pin "2") (pinfunction "2_2") (pintype "passive"))
      (node (ref "D6") (pin "C") (pinfunction "C_C") (pintype "passive"))
      (node (ref "E16") (pin "10") (pinfunction "I1_10") (pintype "input"))
      (node (ref "E16") (pin "9") (pinfunction "I0_9") (pintype "input"))
      (node (ref "R7") (pin "2") (pinfunction "2_2") (pintype "passive"))
    )
    (net (code "77") (name "Net-(E16C-O)") (class "Default")
      (node (ref "E16") (pin "8") (pinfunction "O_8") (pintype "output"))
      (node (ref "E20") (pin "1") (pinfunction "I0_1") (pintype "input"))
      (node (ref "E20") (pin "2") (pinfunction "I1_2") (pintype "input"))
      (node (ref "E20") (pin "4") (pinfunction "I2_4") (pintype "input"))
      (node (ref "E20") (pin "5") (pinfunction "I3_5") (pintype "input"))
    )
    (net (code "78") (name "Net-(E16D-O)") (class "Default")
      (node (ref "E16") (pin "11") (pinfunction "O_11") (pintype "output"))
      (node (ref "E17") (pin "1") (pinfunction "CLR_1") (pintype "input"))
      (node (ref "E17") (pin "13") (pinfunction "CLR_13") (pintype "input"))
      (node (ref "E21") (pin "12") (pinfunction "I0_12") (pintype "input"))
      (node (ref "E21") (pin "13") (pinfunction "I1_13") (pintype "input"))
      (node (ref "E21") (pin "2") (pinfunction "I1_2") (pintype "input"))
    )
    (net (code "79") (name "Net-(E17A-CLK)") (class "Default")
      (node (ref "E17") (pin "12") (pinfunction "D_12") (pintype "input"))
      (node (ref "E17") (pin "3") (pinfunction "CLK_3") (pintype "input"))
      (node (ref "E17") (pin "8") (pinfunction "~{Q}_8") (pintype "output"))
    )
    (net (code "80") (name "Net-(E17A-D)") (class "Default")
      (node (ref "E17") (pin "2") (pinfunction "D_2") (pintype "input"))
      (node (ref "E17") (pin "6") (pinfunction "~{Q}_6") (pintype "output"))
      (node (ref "U$2") (pin "BS1") (pinfunction "1_BS1") (pintype "bidirectional"))
    )
    (net (code "81") (name "Net-(E17A-Q)") (class "Default")
      (node (ref "E17") (pin "5") (pinfunction "Q_5") (pintype "output"))
      (node (ref "U$2") (pin "BT2") (pinfunction "1_BT2") (pintype "bidirectional"))
    )
    (net (code "82") (name "Net-(E17B-CLK)") (class "Default")
      (node (ref "E17") (pin "11") (pinfunction "CLK_11") (pintype "input"))
      (node (ref "E2") (pin "6") (pinfunction "~{Q}_6") (pintype "output"))
    )
    (net (code "83") (name "Net-(E18A-X)") (class "Default")
      (node (ref "E18") (pin "10") (pinfunction "X_10") (pintype "output"))
      (node (ref "E18") (pin "11") (pinfunction "X_11") (pintype "output"))
      (node (ref "R5") (pin "2") (pinfunction "2_2") (pintype "passive"))
    )
    (net (code "84") (name "Net-(E18A-~{X})") (class "Default")
      (node (ref "E18") (pin "12") (pinfunction "~{X}_12") (pintype "output"))
      (node (ref "E18") (pin "4") (pinfunction "A_4") (pintype "input"))
      (node (ref "E18") (pin "5") (pinfunction "B_5") (pintype "input"))
      (node (ref "E18") (pin "6") (pinfunction "C_6") (pintype "input"))
      (node (ref "E18") (pin "8") (pinfunction "D_8") (pintype "input"))
    )
    (net (code "85") (name "Net-(E19A-CLK)") (class "Default")
      (node (ref "E19") (pin "11") (pinfunction "CLK_11") (pintype "input"))
      (node (ref "E19") (pin "3") (pinfunction "CLK_3") (pintype "input"))
      (node (ref "U$2") (pin "BP2") (pinfunction "1_BP2") (pintype "bidirectional"))
    )
    (net (code "86") (name "Net-(E19A-PRE)") (class "Default")
      (node (ref "E19") (pin "10") (pinfunction "PRE_10") (pintype "input"))
      (node (ref "E19") (pin "4") (pinfunction "PRE_4") (pintype "input"))
      (node (ref "U$2") (pin "BP1") (pinfunction "1_BP1") (pintype "bidirectional"))
    )
    (net (code "87") (name "Net-(E19A-Q)") (class "Default")
      (node (ref "E19") (pin "12") (pinfunction "D_12") (pintype "input"))
      (node (ref "E19") (pin "5") (pinfunction "Q_5") (pintype "output"))
    )
    (net (code "88") (name "Net-(E19A-~{Q})") (class "Default")
      (node (ref "E19") (pin "6") (pinfunction "~{Q}_6") (pintype "output"))
      (node (ref "U$2") (pin "BU2") (pinfunction "1_BU2") (pintype "bidirectional"))
    )
    (net (code "89") (name "Net-(E19B-~{Q})") (class "Default")
      (node (ref "E19") (pin "8") (pinfunction "~{Q}_8") (pintype "output"))
      (node (ref "U$2") (pin "BV2") (pinfunction "1_BV2") (pintype "bidirectional"))
    )
    (net (code "90") (name "Net-(E20B-I1)") (class "Default")
      (node (ref "E20") (pin "10") (pinfunction "I1_10") (pintype "input"))
      (node (ref "E21") (pin "11") (pinfunction "O_11") (pintype "output"))
    )
    (net (code "91") (name "Net-(E21A-I0)") (class "Default")
      (node (ref "E2") (pin "5") (pinfunction "Q_5") (pintype "output"))
      (node (ref "E21") (pin "1") (pinfunction "I0_1") (pintype "input"))
    )
    (net (code "92") (name "Net-(E21A-O)") (class "Default")
      (node (ref "E2") (pin "2") (pinfunction "D_2") (pintype "input"))
      (node (ref "E21") (pin "3") (pinfunction "O_3") (pintype "output"))
    )
    (net (code "93") (name "Net-(E21B-I0)") (class "Default")
      (node (ref "E21") (pin "4") (pinfunction "I0_4") (pintype "input"))
      (node (ref "U$2") (pin "BM1") (pinfunction "1_BM1") (pintype "bidirectional"))
    )
    (net (code "94") (name "Net-(E21B-O)") (class "Default")
      (node (ref "E21") (pin "6") (pinfunction "O_6") (pintype "output"))
      (node (ref "U$2") (pin "BN1") (pinfunction "1_BN1") (pintype "bidirectional"))
    )
    (net (code "95") (name "Net-(Q1-E)") (class "Default")
      (node (ref "D5") (pin "A") (pinfunction "A_A") (pintype "passive"))
      (node (ref "Q1") (pin "1") (pinfunction "E_1") (pintype "passive"))
      (node (ref "R6") (pin "1") (pinfunction "1_1") (pintype "passive"))
    )
    (net (code "96") (name "VCC") (class "Default")
      (node (ref "C1") (pin "1") (pinfunction "1_1") (pintype "passive"))
      (node (ref "C10") (pin "1") (pinfunction "1_1") (pintype "passive"))
      (node (ref "C11") (pin "1") (pinfunction "1_1") (pintype "passive"))
      (node (ref "C12") (pin "1") (pinfunction "1_1") (pintype "passive"))
      (node (ref "C13") (pin "1") (pinfunction "1_1") (pintype "passive"))
      (node (ref "C14") (pin "1") (pinfunction "1_1") (pintype "passive"))
      (node (ref "C15") (pin "1") (pinfunction "1_1") (pintype "passive"))
      (node (ref "C16") (pin "1") (pinfunction "1_1") (pintype "passive"))
      (node (ref "C17") (pin "1") (pinfunction "1_1") (pintype "passive"))
      (node (ref "C18") (pin "1") (pinfunction "1_1") (pintype "passive"))
      (node (ref "C19") (pin "1") (pinfunction "1_1") (pintype "passive"))
      (node (ref "C2") (pin "1") (pinfunction "1_1") (pintype "passive"))
      (node (ref "C20") (pin "1") (pinfunction "1_1") (pintype "passive"))
      (node (ref "C21") (pin "1") (pinfunction "1_1") (pintype "passive"))
      (node (ref "C22") (pin "1") (pinfunction "1_1") (pintype "passive"))
      (node (ref "C23") (pin "1") (pinfunction "1_1") (pintype "passive"))
      (node (ref "C26") (pin "1") (pinfunction "1_1") (pintype "passive"))
      (node (ref "C3") (pin "1") (pinfunction "1_1") (pintype "passive"))
      (node (ref "C4") (pin "1") (pinfunction "1_1") (pintype "passive"))
      (node (ref "C5") (pin "1") (pinfunction "1_1") (pintype "passive"))
      (node (ref "C6") (pin "1") (pinfunction "1_1") (pintype "passive"))
      (node (ref "C7") (pin "1") (pinfunction "1_1") (pintype "passive"))
      (node (ref "C8") (pin "1") (pinfunction "1_1") (pintype "passive"))
      (node (ref "C9") (pin "1") (pinfunction "1_1") (pintype "passive"))
      (node (ref "D2") (pin "C") (pinfunction "C_C") (pintype "passive"))
      (node (ref "R2") (pin "2") (pinfunction "2_2") (pintype "passive"))
      (node (ref "R3") (pin "2") (pinfunction "2_2") (pintype "passive"))
      (node (ref "R4") (pin "2") (pinfunction "2_2") (pintype "passive"))
      (node (ref "R6") (pin "2") (pinfunction "2_2") (pintype "passive"))
      (node (ref "R8") (pin "2") (pinfunction "2_2") (pintype "passive"))
      (node (ref "R9") (pin "2") (pinfunction "2_2") (pintype "passive"))
      (node (ref "U$2") (pin "AA2") (pinfunction "1_AA2") (pintype "bidirectional"))
      (node (ref "U$2") (pin "BA2") (pinfunction "1_BA2") (pintype "bidirectional"))
    )
    (net (code "97") (name "unconnected-(E5B-~{Q}-Pad8)") (class "Default")
      (node (ref "E5") (pin "8") (pinfunction "~{Q}_8") (pintype "output"))
    )
    (net (code "98") (name "unconnected-(E6A-~{Q}-Pad6)") (class "Default")
      (node (ref "E6") (pin "6") (pinfunction "~{Q}_6") (pintype "output"))
    )
    (net (code "99") (name "unconnected-(E6B-~{Q}-Pad8)") (class "Default")
      (node (ref "E6") (pin "8") (pinfunction "~{Q}_8") (pintype "output"))
    )
    (net (code "100") (name "unconnected-(E8A-~{Q}-Pad6)") (class "Default")
      (node (ref "E8") (pin "6") (pinfunction "~{Q}_6") (pintype "output"))
    )
    (net (code "101") (name "unconnected-(E8B-~{Q}-Pad8)") (class "Default")
      (node (ref "E8") (pin "8") (pinfunction "~{Q}_8") (pintype "output"))
    )
    (net (code "102") (name "unconnected-(E10A-~{Q}-Pad6)") (class "Default")
      (node (ref "E10") (pin "6") (pinfunction "~{Q}_6") (pintype "output"))
    )
    (net (code "103") (name "unconnected-(E10B-~{Q}-Pad8)") (class "Default")
      (node (ref "E10") (pin "8") (pinfunction "~{Q}_8") (pintype "output"))
    )
    (net (code "104") (name "unconnected-(E13B-~{Q}-Pad8)") (class "Default")
      (node (ref "E13") (pin "8") (pinfunction "~{Q}_8") (pintype "output"))
    )
    (net (code "105") (name "unconnected-(E17B-Q-Pad9)") (class "Default")
      (node (ref "E17") (pin "9") (pinfunction "Q_9") (pintype "output"))
    )
    (net (code "106") (name "unconnected-(E19B-Q-Pad9)") (class "Default")
      (node (ref "E19") (pin "9") (pinfunction "Q_9") (pintype "output"))
    )
  )
)
